# FDCAN_QSPI.net
KiCad netlist of a schematic drawn in Altium Designer
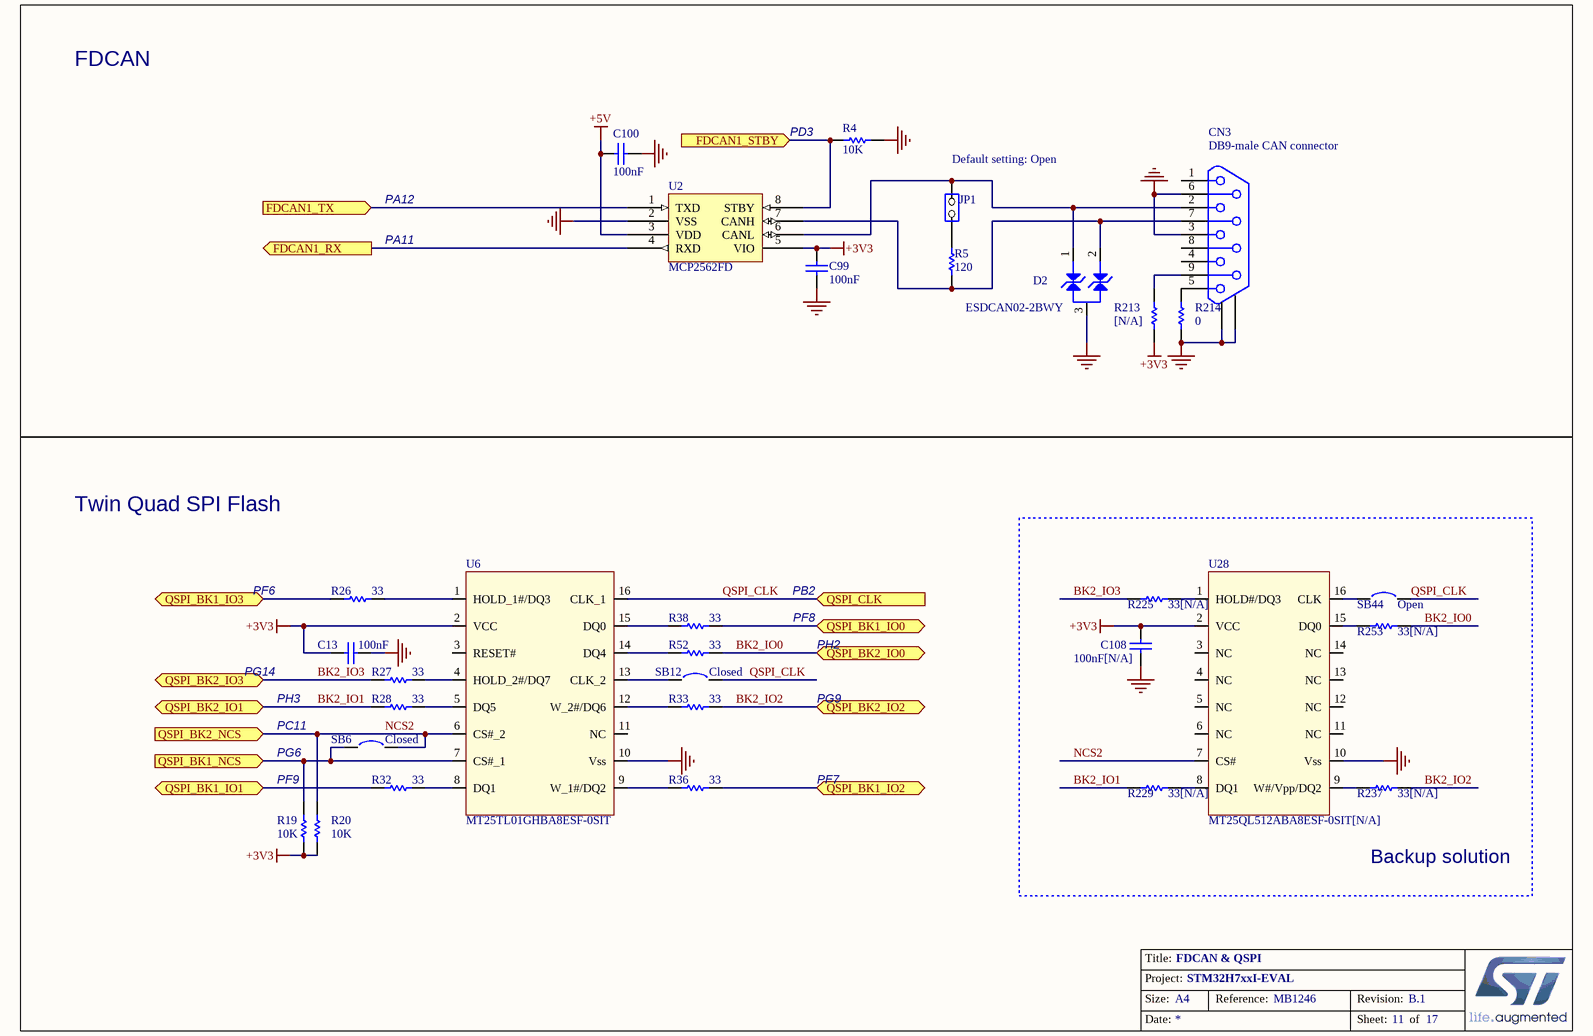
[diagram p0: FDCAN&QSPI.SchDoc]

(export (version "E")
  (design (tool "Eeschema 10.0.6"))
  (components
    (comp (ref "C13")
      (value "100nF")
      (footprint "0402C")
      (description "Capacitor")
      (fields (field (name "PUBLISHER") "Altium Limited"))
      (libsource (lib "Miscellaneous Devices") (part "Cap"))
    )
    (comp (ref "C99")
      (value "100nF")
      (footprint "0603C")
      (description "Capacitor")
      (fields (field (name "PUBLISHER") "Altium Limited"))
      (libsource (lib "Miscellaneous Devices") (part "Cap"))
    )
    (comp (ref "C100")
      (value "100nF")
      (footprint "0603C")
      (description "Capacitor")
      (fields (field (name "PUBLISHER") "Altium Limited"))
      (libsource (lib "Miscellaneous Devices") (part "Cap"))
    )
    (comp (ref "C108")
      (value "100nF[N/A]")
      (footprint "0402C")
      (description "Capacitor")
      (fields (field (name "PUBLISHER") "Altium Limited"))
      (libsource (lib "Miscellaneous Devices") (part "Cap"))
    )
    (comp (ref "CN3")
      (value "DB9-male CAN connector")
      (footprint "DB9/M")
      (libsource (lib "mb1045") (part "DB9-CAN"))
    )
    (comp (ref "D2")
      (value "ESDCAN02-2BWY")
      (footprint "SOT-323")
      (libsource (lib "MB1246") (part "ESDCAN02-2BWY"))
    )
    (comp (ref "JP1") (value "~") (footprint "SIP2") (libsource (lib "*") (part "JP2")))
    (comp (ref "R4")
      (value "10K")
      (footprint "0603R")
      (description "Resistor")
      (fields (field (name "PUBLISHER") "Altium Limited"))
      (libsource (lib "Miscellaneous Devices") (part "Res1"))
    )
    (comp (ref "R5")
      (value "120")
      (footprint "0603R")
      (description "Resistor")
      (fields (field (name "PUBLISHER") "Altium Limited"))
      (libsource (lib "Miscellaneous Devices") (part "res1"))
    )
    (comp (ref "R19")
      (value "10K")
      (footprint "0402R")
      (description "Resistor")
      (fields (field (name "PUBLISHER") "Altium Limited"))
      (libsource (lib "Miscellaneous Devices") (part "res1"))
    )
    (comp (ref "R20")
      (value "10K")
      (footprint "0402R")
      (description "Resistor")
      (fields (field (name "PUBLISHER") "Altium Limited"))
      (libsource (lib "Miscellaneous Devices") (part "res1"))
    )
    (comp (ref "R26")
      (value "33")
      (footprint "0603R")
      (description "Resistor")
      (fields (field (name "PUBLISHER") "Altium Limited"))
      (libsource (lib "Miscellaneous Devices") (part "Res1"))
    )
    (comp (ref "R27")
      (value "33")
      (footprint "0603R")
      (description "Resistor")
      (fields (field (name "PUBLISHER") "Altium Limited"))
      (libsource (lib "Miscellaneous Devices") (part "Res1"))
    )
    (comp (ref "R28")
      (value "33")
      (footprint "0603R")
      (description "Resistor")
      (fields (field (name "PUBLISHER") "Altium Limited"))
      (libsource (lib "Miscellaneous Devices") (part "Res1"))
    )
    (comp (ref "R32")
      (value "33")
      (footprint "0603R")
      (description "Resistor")
      (fields (field (name "PUBLISHER") "Altium Limited"))
      (libsource (lib "Miscellaneous Devices") (part "Res1"))
    )
    (comp (ref "R33")
      (value "33")
      (footprint "0603R")
      (description "Resistor")
      (fields (field (name "PUBLISHER") "Altium Limited"))
      (libsource (lib "Miscellaneous Devices") (part "Res1"))
    )
    (comp (ref "R36")
      (value "33")
      (footprint "0603R")
      (description "Resistor")
      (fields (field (name "PUBLISHER") "Altium Limited"))
      (libsource (lib "Miscellaneous Devices") (part "Res1"))
    )
    (comp (ref "R38")
      (value "33")
      (footprint "0603R")
      (description "Resistor")
      (fields (field (name "PUBLISHER") "Altium Limited"))
      (libsource (lib "Miscellaneous Devices") (part "Res1"))
    )
    (comp (ref "R52")
      (value "33")
      (footprint "0603R")
      (description "Resistor")
      (fields (field (name "PUBLISHER") "Altium Limited"))
      (libsource (lib "Miscellaneous Devices") (part "Res1"))
    )
    (comp (ref "R213")
      (value "[N/A]")
      (footprint "0603R")
      (description "Resistor")
      (fields (field (name "PUBLISHER") "Altium Limited"))
      (libsource (lib "Miscellaneous Devices") (part "res1"))
    )
    (comp (ref "R214")
      (value "0")
      (footprint "0603R")
      (description "Resistor")
      (fields (field (name "PUBLISHER") "Altium Limited"))
      (libsource (lib "Miscellaneous Devices") (part "res1"))
    )
    (comp (ref "R225")
      (value "33[N/A]")
      (footprint "0603R")
      (description "Resistor")
      (fields (field (name "PUBLISHER") "Altium Limited"))
      (libsource (lib "Miscellaneous Devices") (part "Res1"))
    )
    (comp (ref "R229")
      (value "33[N/A]")
      (footprint "0603R")
      (description "Resistor")
      (fields (field (name "PUBLISHER") "Altium Limited"))
      (libsource (lib "Miscellaneous Devices") (part "Res1"))
    )
    (comp (ref "R237")
      (value "33[N/A]")
      (footprint "0603R")
      (description "Resistor")
      (fields (field (name "PUBLISHER") "Altium Limited"))
      (libsource (lib "Miscellaneous Devices") (part "Res1"))
    )
    (comp (ref "R253")
      (value "33[N/A]")
      (footprint "0603R")
      (description "Resistor")
      (fields (field (name "PUBLISHER") "Altium Limited"))
      (libsource (lib "Miscellaneous Devices") (part "Res1"))
    )
    (comp (ref "SB6")
      (value "Closed")
      (footprint "SB_0603")
      (description "Circuit Breaker")
      (fields (field (name "PUBLISHER") "Altium Limited"))
      (libsource (lib "MB1165") (part "Circuit Breaker_close"))
    )
    (comp (ref "SB12")
      (value "Closed")
      (footprint "SB_0603")
      (description "Circuit Breaker")
      (fields (field (name "PUBLISHER") "Altium Limited"))
      (libsource (lib "MB1165") (part "Circuit Breaker_close"))
    )
    (comp (ref "SB44")
      (value "Open")
      (footprint "SB_0603")
      (description "Circuit Breaker")
      (fields (field (name "PUBLISHER") "Altium Limited"))
      (libsource (lib "MB1165") (part "Circuit Breaker"))
    )
    (comp (ref "U2")
      (value "MCP2562FD")
      (footprint "SOIC8_1R27_4R9X6")
      (description "CAN Flexible Data Rate Transceiver")
      (libsource (lib "MB1246") (part "MCP2562FD"))
    )
    (comp (ref "U6")
      (value "MT25TL01GHBA8ESF-0SIT")
      (footprint "SOIC16W_1R27_10R3X10R33")
      (description "Serial NOR Flash Memory")
      (libsource (lib "MB1246") (part "MT25TL01GHBA8ESF-0SIT"))
    )
    (comp (ref "U28")
      (value "MT25QL512ABA8ESF-0SIT[N/A]")
      (footprint "SOIC16W_1R27_10R3X10R33")
      (libsource (lib "MB1167") (part "QSPI_16pins"))
    )
  )
  (nets
    (net (code "1") (name "+3V3") (class "Default")
      (node (ref "C108") (pin "1") (pinfunction "1_1") (pintype "passive"))
      (node (ref "C13") (pin "1") (pinfunction "1_1") (pintype "passive"))
      (node (ref "C99") (pin "1") (pinfunction "1_1") (pintype "passive"))
      (node (ref "R19") (pin "2") (pinfunction "2_2") (pintype "passive"))
      (node (ref "R20") (pin "2") (pinfunction "2_2") (pintype "passive"))
      (node (ref "R213") (pin "1") (pinfunction "1_1") (pintype "passive"))
      (node (ref "U2") (pin "5") (pinfunction "VIO_5") (pintype "power_in"))
      (node (ref "U28") (pin "2") (pinfunction "VCC_2") (pintype "passive"))
      (node (ref "U6") (pin "2") (pinfunction "VCC_2") (pintype "passive"))
    )
    (net (code "2") (name "+5V") (class "Default")
      (node (ref "C100") (pin "1") (pinfunction "1_1") (pintype "passive"))
      (node (ref "U2") (pin "3") (pinfunction "VDD_3") (pintype "power_in"))
    )
    (net (code "3") (name "/BK2_IO0") (class "Default")
      (node (ref "R253") (pin "1") (pinfunction "1_1") (pintype "passive"))
      (node (ref "R52") (pin "1") (pinfunction "1_1") (pintype "passive"))
    )
    (net (code "4") (name "/BK2_IO1") (class "Default")
      (node (ref "R229") (pin "2") (pinfunction "2_2") (pintype "passive"))
      (node (ref "R28") (pin "2") (pinfunction "2_2") (pintype "passive"))
    )
    (net (code "5") (name "/BK2_IO2") (class "Default")
      (node (ref "R237") (pin "1") (pinfunction "1_1") (pintype "passive"))
      (node (ref "R33") (pin "1") (pinfunction "1_1") (pintype "passive"))
    )
    (net (code "6") (name "/BK2_IO3") (class "Default")
      (node (ref "R225") (pin "2") (pinfunction "2_2") (pintype "passive"))
      (node (ref "R27") (pin "2") (pinfunction "2_2") (pintype "passive"))
    )
    (net (code "7") (name "/FDCAN1_RX") (class "Default")
      (node (ref "U2") (pin "4") (pinfunction "RXD_4") (pintype "output"))
    )
    (net (code "8") (name "/FDCAN1_STBY") (class "Default")
      (node (ref "R4") (pin "1") (pinfunction "1_1") (pintype "passive"))
      (node (ref "U2") (pin "8") (pinfunction "STBY_8") (pintype "input"))
    )
    (net (code "9") (name "/FDCAN1_TX") (class "Default")
      (node (ref "U2") (pin "1") (pinfunction "TXD_1") (pintype "input"))
    )
    (net (code "10") (name "/NCS2") (class "Default")
      (node (ref "R20") (pin "1") (pinfunction "1_1") (pintype "passive"))
      (node (ref "SB6") (pin "2") (pinfunction "2_2") (pintype "passive"))
      (node (ref "U28") (pin "7") (pinfunction "CS#_7") (pintype "passive"))
      (node (ref "U6") (pin "6") (pinfunction "CS#_2_6") (pintype "passive"))
    )
    (net (code "11") (name "/QSPI_BK1_IO0") (class "Default")
      (node (ref "R38") (pin "1") (pinfunction "1_1") (pintype "passive"))
    )
    (net (code "12") (name "/QSPI_BK1_IO1") (class "Default")
      (node (ref "R32") (pin "2") (pinfunction "2_2") (pintype "passive"))
    )
    (net (code "13") (name "/QSPI_BK1_IO2") (class "Default")
      (node (ref "R36") (pin "1") (pinfunction "1_1") (pintype "passive"))
    )
    (net (code "14") (name "/QSPI_BK1_IO3") (class "Default")
      (node (ref "R26") (pin "2") (pinfunction "2_2") (pintype "passive"))
    )
    (net (code "15") (name "/QSPI_BK1_NCS") (class "Default")
      (node (ref "R19") (pin "1") (pinfunction "1_1") (pintype "passive"))
      (node (ref "SB6") (pin "1") (pinfunction "1_1") (pintype "passive"))
      (node (ref "U6") (pin "7") (pinfunction "CS#_1_7") (pintype "passive"))
    )
    (net (code "16") (name "/QSPI_CLK") (class "Default")
      (node (ref "SB12") (pin "2") (pinfunction "2_2") (pintype "passive"))
      (node (ref "SB44") (pin "2") (pinfunction "2_2") (pintype "passive"))
      (node (ref "U6") (pin "16") (pinfunction "CLK_1_16") (pintype "passive"))
    )
    (net (code "17") (name "GND") (class "Default")
      (node (ref "C100") (pin "2") (pinfunction "2_2") (pintype "passive"))
      (node (ref "C108") (pin "2") (pinfunction "2_2") (pintype "passive"))
      (node (ref "C13") (pin "2") (pinfunction "2_2") (pintype "passive"))
      (node (ref "C99") (pin "2") (pinfunction "2_2") (pintype "passive"))
      (node (ref "CN3") (pin "10") (pinfunction "10_10") (pintype "passive"))
      (node (ref "CN3") (pin "11") (pinfunction "11_11") (pintype "passive"))
      (node (ref "CN3") (pin "3") (pinfunction "3_3") (pintype "passive"))
      (node (ref "CN3") (pin "6") (pinfunction "6_6") (pintype "passive"))
      (node (ref "D2") (pin "3") (pinfunction "3_3") (pintype "passive"))
      (node (ref "R214") (pin "1") (pinfunction "1_1") (pintype "passive"))
      (node (ref "R4") (pin "2") (pinfunction "2_2") (pintype "passive"))
      (node (ref "U2") (pin "2") (pinfunction "VSS_2") (pintype "power_in"))
      (node (ref "U28") (pin "10") (pinfunction "Vss_10") (pintype "passive"))
      (node (ref "U6") (pin "10") (pinfunction "Vss_10") (pintype "passive"))
    )
    (net (code "18") (name "Net-(CN3-Pad5)") (class "Default")
      (node (ref "CN3") (pin "5") (pinfunction "5_5") (pintype "passive"))
      (node (ref "R214") (pin "2") (pinfunction "2_2") (pintype "passive"))
    )
    (net (code "19") (name "Net-(CN3-Pad9)") (class "Default")
      (node (ref "CN3") (pin "9") (pinfunction "9_9") (pintype "passive"))
      (node (ref "R213") (pin "2") (pinfunction "2_2") (pintype "passive"))
    )
    (net (code "20") (name "Net-(JP1-COMMON)") (class "Default")
      (node (ref "JP1") (pin "1") (pinfunction "COMMON_1") (pintype "passive"))
      (node (ref "R5") (pin "2") (pinfunction "2_2") (pintype "passive"))
    )
    (net (code "21") (name "Net-(JP1-NO)") (class "Default")
      (node (ref "CN3") (pin "2") (pinfunction "2_2") (pintype "passive"))
      (node (ref "D2") (pin "1") (pinfunction "1_1") (pintype "passive"))
      (node (ref "JP1") (pin "2") (pinfunction "NO_2") (pintype "passive"))
      (node (ref "U2") (pin "6") (pinfunction "CANL_6") (pintype "bidirectional"))
    )
    (net (code "22") (name "Net-(U2-CANH)") (class "Default")
      (node (ref "CN3") (pin "7") (pinfunction "7_7") (pintype "passive"))
      (node (ref "D2") (pin "2") (pinfunction "2_2") (pintype "passive"))
      (node (ref "R5") (pin "1") (pinfunction "1_1") (pintype "passive"))
      (node (ref "U2") (pin "7") (pinfunction "CANH_7") (pintype "bidirectional"))
    )
    (net (code "23") (name "Net-(U6-CLK_2)") (class "Default")
      (node (ref "SB12") (pin "1") (pinfunction "1_1") (pintype "passive"))
      (node (ref "U6") (pin "13") (pinfunction "CLK_2_13") (pintype "passive"))
    )
    (net (code "24") (name "Net-(U6-DQ0)") (class "Default")
      (node (ref "R38") (pin "2") (pinfunction "2_2") (pintype "passive"))
      (node (ref "U6") (pin "15") (pinfunction "DQ0_15") (pintype "passive"))
    )
    (net (code "25") (name "Net-(U6-DQ1)") (class "Default")
      (node (ref "R32") (pin "1") (pinfunction "1_1") (pintype "passive"))
      (node (ref "U6") (pin "8") (pinfunction "DQ1_8") (pintype "passive"))
    )
    (net (code "26") (name "Net-(U6-DQ4)") (class "Default")
      (node (ref "R52") (pin "2") (pinfunction "2_2") (pintype "passive"))
      (node (ref "U6") (pin "14") (pinfunction "DQ4_14") (pintype "passive"))
    )
    (net (code "27") (name "Net-(U6-DQ5)") (class "Default")
      (node (ref "R28") (pin "1") (pinfunction "1_1") (pintype "passive"))
      (node (ref "U6") (pin "5") (pinfunction "DQ5_5") (pintype "passive"))
    )
    (net (code "28") (name "Net-(U6-HOLD_1#{slash}DQ3)") (class "Default")
      (node (ref "R26") (pin "1") (pinfunction "1_1") (pintype "passive"))
      (node (ref "U6") (pin "1") (pinfunction "HOLD_1#/DQ3_1") (pintype "passive"))
    )
    (net (code "29") (name "Net-(U6-HOLD_2#{slash}DQ7)") (class "Default")
      (node (ref "R27") (pin "1") (pinfunction "1_1") (pintype "passive"))
      (node (ref "U6") (pin "4") (pinfunction "HOLD_2#/DQ7_4") (pintype "passive"))
    )
    (net (code "30") (name "Net-(U6-W_1#{slash}DQ2)") (class "Default")
      (node (ref "R36") (pin "2") (pinfunction "2_2") (pintype "passive"))
      (node (ref "U6") (pin "9") (pinfunction "W_1#/DQ2_9") (pintype "passive"))
    )
    (net (code "31") (name "Net-(U6-W_2#{slash}DQ6)") (class "Default")
      (node (ref "R33") (pin "2") (pinfunction "2_2") (pintype "passive"))
      (node (ref "U6") (pin "12") (pinfunction "W_2#/DQ6_12") (pintype "passive"))
    )
    (net (code "32") (name "Net-(U28-CLK)") (class "Default")
      (node (ref "SB44") (pin "1") (pinfunction "1_1") (pintype "passive"))
      (node (ref "U28") (pin "16") (pinfunction "CLK_16") (pintype "passive"))
    )
    (net (code "33") (name "Net-(U28-DQ0)") (class "Default")
      (node (ref "R253") (pin "2") (pinfunction "2_2") (pintype "passive"))
      (node (ref "U28") (pin "15") (pinfunction "DQ0_15") (pintype "passive"))
    )
    (net (code "34") (name "Net-(U28-DQ1)") (class "Default")
      (node (ref "R229") (pin "1") (pinfunction "1_1") (pintype "passive"))
      (node (ref "U28") (pin "8") (pinfunction "DQ1_8") (pintype "passive"))
    )
    (net (code "35") (name "Net-(U28-HOLD#{slash}DQ3)") (class "Default")
      (node (ref "R225") (pin "1") (pinfunction "1_1") (pintype "passive"))
      (node (ref "U28") (pin "1") (pinfunction "HOLD#/DQ3_1") (pintype "passive"))
    )
    (net (code "36") (name "Net-(U28-W#{slash}Vpp{slash}DQ2)") (class "Default")
      (node (ref "R237") (pin "2") (pinfunction "2_2") (pintype "passive"))
      (node (ref "U28") (pin "9") (pinfunction "W#/Vpp/DQ2_9") (pintype "passive"))
    )
    (net (code "37") (name "unconnected-(CN3-Pad1)") (class "Default")
      (node (ref "CN3") (pin "1") (pinfunction "1_1") (pintype "passive"))
    )
    (net (code "38") (name "unconnected-(CN3-Pad4)") (class "Default")
      (node (ref "CN3") (pin "4") (pinfunction "4_4") (pintype "passive"))
    )
    (net (code "39") (name "unconnected-(CN3-Pad8)") (class "Default")
      (node (ref "CN3") (pin "8") (pinfunction "8_8") (pintype "passive"))
    )
    (net (code "40") (name "unconnected-(U6-NC-Pad11)") (class "Default")
      (node (ref "U6") (pin "11") (pinfunction "NC_11") (pintype "passive"))
    )
    (net (code "41") (name "unconnected-(U6-RESET#-Pad3)") (class "Default")
      (node (ref "U6") (pin "3") (pinfunction "RESET#_3") (pintype "passive"))
    )
    (net (code "42") (name "unconnected-(U28-NC-Pad3)") (class "Default")
      (node (ref "U28") (pin "3") (pinfunction "NC_3") (pintype "passive"))
    )
    (net (code "43") (name "unconnected-(U28-NC-Pad4)") (class "Default")
      (node (ref "U28") (pin "4") (pinfunction "NC_4") (pintype "passive"))
    )
    (net (code "44") (name "unconnected-(U28-NC-Pad5)") (class "Default")
      (node (ref "U28") (pin "5") (pinfunction "NC_5") (pintype "passive"))
    )
    (net (code "45") (name "unconnected-(U28-NC-Pad6)") (class "Default")
      (node (ref "U28") (pin "6") (pinfunction "NC_6") (pintype "passive"))
    )
    (net (code "46") (name "unconnected-(U28-NC-Pad11)") (class "Default")
      (node (ref "U28") (pin "11") (pinfunction "NC_11") (pintype "passive"))
    )
    (net (code "47") (name "unconnected-(U28-NC-Pad12)") (class "Default")
      (node (ref "U28") (pin "12") (pinfunction "NC_12") (pintype "passive"))
    )
    (net (code "48") (name "unconnected-(U28-NC-Pad13)") (class "Default")
      (node (ref "U28") (pin "13") (pinfunction "NC_13") (pintype "passive"))
    )
    (net (code "49") (name "unconnected-(U28-NC-Pad14)") (class "Default")
      (node (ref "U28") (pin "14") (pinfunction "NC_14") (pintype "passive"))
    )
  )
)
